# PrototypeVar4_Compactimization.net
KiCad netlist of a schematic drawn in EAGLE
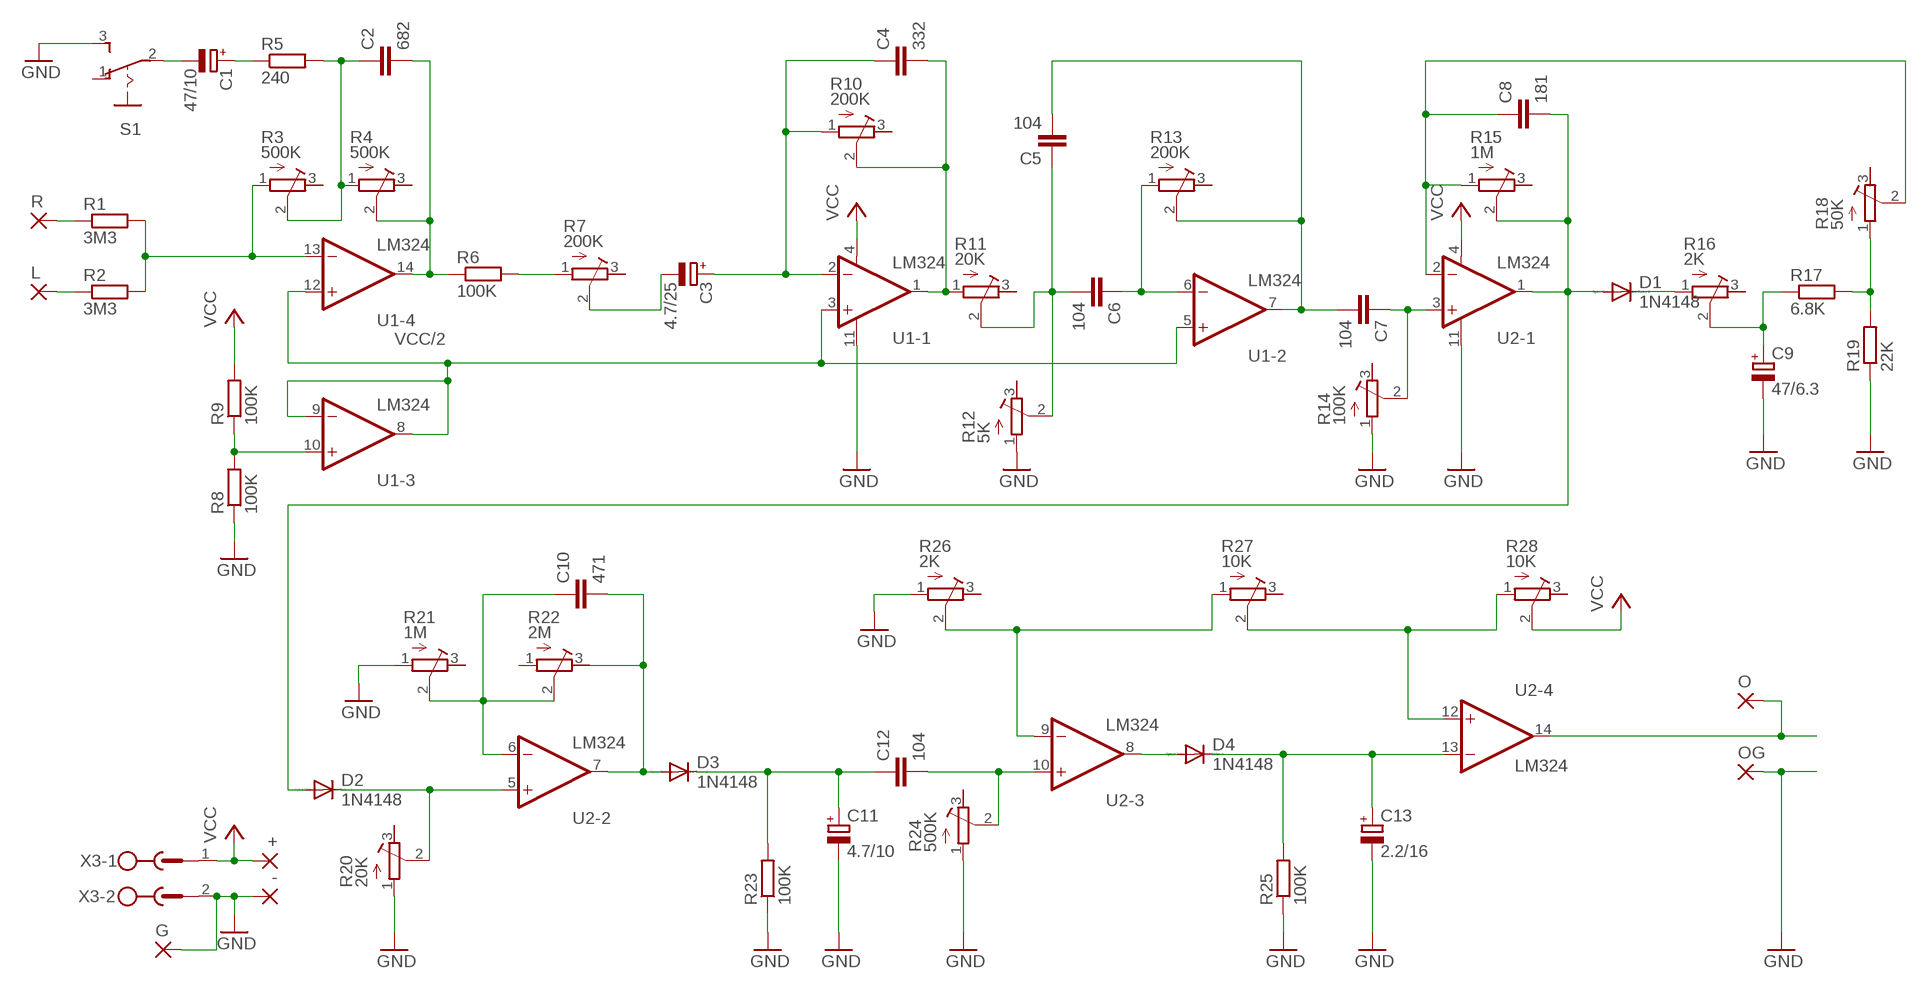
[diagram p0: schematic, sheet 1]

(export (version "E")
  (design (tool "Eeschema 10.0.6"))
  (components
    (comp (ref "+")
      (value "1,6/0,9")
      (footprint "eagle-import:1,6_0,9")
      (libsource (lib "eagle-import") (part "1,6/0,9"))
    )
    (comp (ref "-")
      (value "1,6/0,9")
      (footprint "eagle-import:1,6_0,9")
      (libsource (lib "eagle-import") (part "1,6/0,9"))
    )
    (comp (ref "C1")
      (value "47/10")
      (footprint "eagle-import:E2,5-7")
      (libsource (lib "eagle-import") (part "CPOL-EUE2.5-7"))
    )
    (comp (ref "C2")
      (value "682")
      (footprint "eagle-import:C050-035X075")
      (libsource (lib "eagle-import") (part "C-EU050-035X075"))
    )
    (comp (ref "C3")
      (value "4.7/25")
      (footprint "eagle-import:E2,5-7")
      (libsource (lib "eagle-import") (part "CPOL-EUE2.5-7"))
    )
    (comp (ref "C4")
      (value "332")
      (footprint "eagle-import:C050-035X075")
      (libsource (lib "eagle-import") (part "C-EU050-035X075"))
    )
    (comp (ref "C5")
      (value "104")
      (footprint "eagle-import:C050-035X075")
      (libsource (lib "eagle-import") (part "C-EU050-035X075"))
    )
    (comp (ref "C6")
      (value "104")
      (footprint "eagle-import:C050-035X075")
      (libsource (lib "eagle-import") (part "C-EU050-035X075"))
    )
    (comp (ref "C7")
      (value "104")
      (footprint "eagle-import:C050-035X075")
      (libsource (lib "eagle-import") (part "C-EU050-035X075"))
    )
    (comp (ref "C8")
      (value "181")
      (footprint "eagle-import:C050-035X075")
      (libsource (lib "eagle-import") (part "C-EU050-035X075"))
    )
    (comp (ref "C9")
      (value "47/6.3")
      (footprint "eagle-import:E2,5-7")
      (libsource (lib "eagle-import") (part "CPOL-EUE2.5-7"))
    )
    (comp (ref "C10")
      (value "471")
      (footprint "eagle-import:C050-035X075")
      (libsource (lib "eagle-import") (part "C-EU050-035X075"))
    )
    (comp (ref "C11")
      (value "4.7/10")
      (footprint "eagle-import:E2,5-7")
      (libsource (lib "eagle-import") (part "CPOL-EUE2.5-7"))
    )
    (comp (ref "C12")
      (value "104")
      (footprint "eagle-import:C050-035X075")
      (libsource (lib "eagle-import") (part "C-EU050-035X075"))
    )
    (comp (ref "C13")
      (value "2.2/16")
      (footprint "eagle-import:E2,5-7")
      (libsource (lib "eagle-import") (part "CPOL-EUE2.5-7"))
    )
    (comp (ref "D1")
      (value "1N4148")
      (footprint "eagle-import:DO35-10")
      (libsource (lib "eagle-import") (part "1N4148DO35-10"))
    )
    (comp (ref "D2")
      (value "1N4148")
      (footprint "eagle-import:DO35-10")
      (libsource (lib "eagle-import") (part "1N4148DO35-10"))
    )
    (comp (ref "D3")
      (value "1N4148")
      (footprint "eagle-import:DO35-10")
      (libsource (lib "eagle-import") (part "1N4148DO35-10"))
    )
    (comp (ref "D4")
      (value "1N4148")
      (footprint "eagle-import:DO35-10")
      (libsource (lib "eagle-import") (part "1N4148DO35-10"))
    )
    (comp (ref "G")
      (value "1,6/0,9")
      (footprint "eagle-import:1,6_0,9")
      (libsource (lib "eagle-import") (part "1,6/0,9"))
    )
    (comp (ref "L")
      (value "1,6/0,9")
      (footprint "eagle-import:1,6_0,9")
      (libsource (lib "eagle-import") (part "1,6/0,9"))
    )
    (comp (ref "O")
      (value "1,6/0,9")
      (footprint "eagle-import:1,6_0,9")
      (libsource (lib "eagle-import") (part "1,6/0,9"))
    )
    (comp (ref "OG")
      (value "1,6/0,9")
      (footprint "eagle-import:1,6_0,9")
      (libsource (lib "eagle-import") (part "1,6/0,9"))
    )
    (comp (ref "R")
      (value "1,6/0,8")
      (footprint "eagle-import:1,6_0,8")
      (libsource (lib "eagle-import") (part "1,6/0,8"))
    )
    (comp (ref "R1")
      (value "3M3")
      (footprint "eagle-import:0207_10")
      (libsource (lib "eagle-import") (part "R-EU_0207/10"))
    )
    (comp (ref "R2")
      (value "3M3")
      (footprint "eagle-import:0207_10")
      (libsource (lib "eagle-import") (part "R-EU_0207/10"))
    )
    (comp (ref "R3")
      (value "500K")
      (footprint "eagle-import:RTRIM64W")
      (libsource (lib "eagle-import") (part "R-TRIMM64W"))
    )
    (comp (ref "R4")
      (value "500K")
      (footprint "eagle-import:RTRIM64W")
      (libsource (lib "eagle-import") (part "R-TRIMM64W"))
    )
    (comp (ref "R5")
      (value "240")
      (footprint "eagle-import:0207_10")
      (libsource (lib "eagle-import") (part "R-EU_0207/10"))
    )
    (comp (ref "R6")
      (value "100K")
      (footprint "eagle-import:0207_10")
      (libsource (lib "eagle-import") (part "R-EU_0207/10"))
    )
    (comp (ref "R7")
      (value "200K")
      (footprint "eagle-import:RTRIM64W")
      (libsource (lib "eagle-import") (part "R-TRIMM64W"))
    )
    (comp (ref "R8")
      (value "100K")
      (footprint "eagle-import:0207_10")
      (libsource (lib "eagle-import") (part "R-EU_0207/10"))
    )
    (comp (ref "R9")
      (value "100K")
      (footprint "eagle-import:0207_10")
      (libsource (lib "eagle-import") (part "R-EU_0207/10"))
    )
    (comp (ref "R10")
      (value "200K")
      (footprint "eagle-import:RTRIM64W")
      (libsource (lib "eagle-import") (part "R-TRIMM64W"))
    )
    (comp (ref "R11")
      (value "20K")
      (footprint "eagle-import:RTRIM64W")
      (libsource (lib "eagle-import") (part "R-TRIMM64W"))
    )
    (comp (ref "R12")
      (value "5K")
      (footprint "eagle-import:RTRIM64W")
      (libsource (lib "eagle-import") (part "R-TRIMM64W"))
    )
    (comp (ref "R13")
      (value "200K")
      (footprint "eagle-import:RTRIM64W")
      (libsource (lib "eagle-import") (part "R-TRIMM64W"))
    )
    (comp (ref "R14")
      (value "100K")
      (footprint "eagle-import:RTRIM64W")
      (libsource (lib "eagle-import") (part "R-TRIMM64W"))
    )
    (comp (ref "R15")
      (value "1M")
      (footprint "eagle-import:RTRIM64W")
      (libsource (lib "eagle-import") (part "R-TRIMM64W"))
    )
    (comp (ref "R16")
      (value "2K")
      (footprint "eagle-import:RTRIM64W")
      (libsource (lib "eagle-import") (part "R-TRIMM64W"))
    )
    (comp (ref "R17")
      (value "6.8K")
      (footprint "eagle-import:0207_10")
      (libsource (lib "eagle-import") (part "R-EU_0207/10"))
    )
    (comp (ref "R18")
      (value "50K")
      (footprint "eagle-import:RTRIM64W")
      (libsource (lib "eagle-import") (part "R-TRIMM64W"))
    )
    (comp (ref "R19")
      (value "22K")
      (footprint "eagle-import:0207_10")
      (libsource (lib "eagle-import") (part "R-EU_0207/10"))
    )
    (comp (ref "R20")
      (value "20K")
      (footprint "eagle-import:RTRIM64W")
      (libsource (lib "eagle-import") (part "R-TRIMM64W"))
    )
    (comp (ref "R21")
      (value "1M")
      (footprint "eagle-import:RTRIM64W")
      (libsource (lib "eagle-import") (part "R-TRIMM64W"))
    )
    (comp (ref "R22")
      (value "2M")
      (footprint "eagle-import:RTRIM64W")
      (libsource (lib "eagle-import") (part "R-TRIMM64W"))
    )
    (comp (ref "R23")
      (value "100K")
      (footprint "eagle-import:0207_10")
      (libsource (lib "eagle-import") (part "R-EU_0207/10"))
    )
    (comp (ref "R24")
      (value "500K")
      (footprint "eagle-import:RTRIM64W")
      (libsource (lib "eagle-import") (part "R-TRIMM64W"))
    )
    (comp (ref "R25")
      (value "100K")
      (footprint "eagle-import:0207_10")
      (libsource (lib "eagle-import") (part "R-EU_0207/10"))
    )
    (comp (ref "R26")
      (value "2K")
      (footprint "eagle-import:RTRIM64W")
      (libsource (lib "eagle-import") (part "R-TRIMM64W"))
    )
    (comp (ref "R27")
      (value "10K")
      (footprint "eagle-import:RTRIM64W")
      (libsource (lib "eagle-import") (part "R-TRIMM64W"))
    )
    (comp (ref "R28")
      (value "10K")
      (footprint "eagle-import:RTRIM64W")
      (libsource (lib "eagle-import") (part "R-TRIMM64W"))
    )
    (comp (ref "S1")
      (value "255SB")
      (footprint "eagle-import:255SB")
      (libsource (lib "eagle-import") (part "255SB"))
    )
    (comp (ref "U1-")
      (value "LM324")
      (footprint "eagle-import:SOIC-14")
      (libsource (lib "eagle-import") (part "LM324"))
    )
    (comp (ref "U2-")
      (value "LM324")
      (footprint "eagle-import:SOIC-14")
      (libsource (lib "eagle-import") (part "LM324"))
    )
    (comp (ref "X3")
      (value "MSTBV2")
      (footprint "eagle-import:MSTBV2")
      (libsource (lib "eagle-import") (part "MSTBV2"))
    )
  )
  (nets
    (net (code "1") (name "/VCC{slash}2") (class "Default")
      (node (ref "U1-") (pin "12") (pinfunction "+IN_12") (pintype "input"))
      (node (ref "U1-") (pin "3") (pinfunction "+IN_3") (pintype "input"))
      (node (ref "U1-") (pin "5") (pinfunction "+IN_5") (pintype "input"))
      (node (ref "U1-") (pin "8") (pinfunction "OUT_8") (pintype "output"))
      (node (ref "U1-") (pin "9") (pinfunction "-IN_9") (pintype "input"))
    )
    (net (code "2") (name "GND") (class "Default")
      (node (ref "-") (pin "1") (pinfunction "P_1") (pintype "passive"))
      (node (ref "C11") (pin "-") (pinfunction "-_-") (pintype "passive"))
      (node (ref "C13") (pin "-") (pinfunction "-_-") (pintype "passive"))
      (node (ref "C9") (pin "-") (pinfunction "-_-") (pintype "passive"))
      (node (ref "G") (pin "1") (pinfunction "P_1") (pintype "passive"))
      (node (ref "OG") (pin "1") (pinfunction "P_1") (pintype "passive"))
      (node (ref "R12") (pin "1") (pinfunction "A_1") (pintype "passive"))
      (node (ref "R14") (pin "1") (pinfunction "A_1") (pintype "passive"))
      (node (ref "R19") (pin "1") (pinfunction "1_1") (pintype "passive"))
      (node (ref "R20") (pin "1") (pinfunction "A_1") (pintype "passive"))
      (node (ref "R21") (pin "1") (pinfunction "A_1") (pintype "passive"))
      (node (ref "R23") (pin "1") (pinfunction "1_1") (pintype "passive"))
      (node (ref "R24") (pin "1") (pinfunction "A_1") (pintype "passive"))
      (node (ref "R25") (pin "1") (pinfunction "1_1") (pintype "passive"))
      (node (ref "R26") (pin "1") (pinfunction "A_1") (pintype "passive"))
      (node (ref "R8") (pin "1") (pinfunction "1_1") (pintype "passive"))
      (node (ref "S1") (pin "3") (pinfunction "S_3") (pintype "passive"))
      (node (ref "U1-") (pin "11") (pinfunction "V-_11") (pintype "power_in"))
      (node (ref "U2-") (pin "11") (pinfunction "V-_11") (pintype "power_in"))
      (node (ref "X3") (pin "2") (pinfunction "SK_2") (pintype "passive"))
    )
    (net (code "3") (name "Net-(C1-Pad+)") (class "Default")
      (node (ref "C1") (pin "+") (pinfunction "+_+") (pintype "passive"))
      (node (ref "R5") (pin "1") (pinfunction "1_1") (pintype "passive"))
    )
    (net (code "4") (name "Net-(C11-Pad+)") (class "Default")
      (node (ref "C11") (pin "+") (pinfunction "+_+") (pintype "passive"))
      (node (ref "C12") (pin "1") (pinfunction "1_1") (pintype "passive"))
      (node (ref "D3") (pin "C") (pinfunction "C_C") (pintype "passive"))
      (node (ref "R23") (pin "2") (pinfunction "2_2") (pintype "passive"))
    )
    (net (code "5") (name "Net-(L-P)") (class "Default")
      (node (ref "L") (pin "1") (pinfunction "P_1") (pintype "passive"))
      (node (ref "R2") (pin "1") (pinfunction "1_1") (pintype "passive"))
    )
    (net (code "6") (name "Net-(O-P)") (class "Default")
      (node (ref "O") (pin "1") (pinfunction "P_1") (pintype "passive"))
      (node (ref "U2-") (pin "14") (pinfunction "OUT_14") (pintype "output"))
    )
    (net (code "7") (name "Net-(R-P)") (class "Default")
      (node (ref "R") (pin "1") (pinfunction "P_1") (pintype "passive"))
      (node (ref "R1") (pin "1") (pinfunction "1_1") (pintype "passive"))
    )
    (net (code "8") (name "Net-(R3-A)") (class "Default")
      (node (ref "R1") (pin "2") (pinfunction "2_2") (pintype "passive"))
      (node (ref "R2") (pin "2") (pinfunction "2_2") (pintype "passive"))
      (node (ref "R3") (pin "1") (pinfunction "A_1") (pintype "passive"))
      (node (ref "U1-") (pin "13") (pinfunction "-IN_13") (pintype "input"))
    )
    (net (code "9") (name "Net-(R3-S)") (class "Default")
      (node (ref "C2") (pin "1") (pinfunction "1_1") (pintype "passive"))
      (node (ref "R3") (pin "2") (pinfunction "S_2") (pintype "passive"))
      (node (ref "R4") (pin "1") (pinfunction "A_1") (pintype "passive"))
      (node (ref "R5") (pin "2") (pinfunction "2_2") (pintype "passive"))
    )
    (net (code "10") (name "Net-(R4-S)") (class "Default")
      (node (ref "C2") (pin "2") (pinfunction "2_2") (pintype "passive"))
      (node (ref "R4") (pin "2") (pinfunction "S_2") (pintype "passive"))
      (node (ref "R6") (pin "1") (pinfunction "1_1") (pintype "passive"))
      (node (ref "U1-") (pin "14") (pinfunction "OUT_14") (pintype "output"))
    )
    (net (code "11") (name "Net-(R7-A)") (class "Default")
      (node (ref "R6") (pin "2") (pinfunction "2_2") (pintype "passive"))
      (node (ref "R7") (pin "1") (pinfunction "A_1") (pintype "passive"))
    )
    (net (code "12") (name "Net-(R7-S)") (class "Default")
      (node (ref "C3") (pin "-") (pinfunction "-_-") (pintype "passive"))
      (node (ref "R7") (pin "2") (pinfunction "S_2") (pintype "passive"))
    )
    (net (code "13") (name "Net-(R10-A)") (class "Default")
      (node (ref "C3") (pin "+") (pinfunction "+_+") (pintype "passive"))
      (node (ref "C4") (pin "1") (pinfunction "1_1") (pintype "passive"))
      (node (ref "R10") (pin "1") (pinfunction "A_1") (pintype "passive"))
      (node (ref "U1-") (pin "2") (pinfunction "-IN_2") (pintype "input"))
    )
    (net (code "14") (name "Net-(R10-S)") (class "Default")
      (node (ref "C4") (pin "2") (pinfunction "2_2") (pintype "passive"))
      (node (ref "R10") (pin "2") (pinfunction "S_2") (pintype "passive"))
      (node (ref "R11") (pin "1") (pinfunction "A_1") (pintype "passive"))
      (node (ref "U1-") (pin "1") (pinfunction "OUT_1") (pintype "output"))
    )
    (net (code "15") (name "Net-(R11-S)") (class "Default")
      (node (ref "C5") (pin "1") (pinfunction "1_1") (pintype "passive"))
      (node (ref "C6") (pin "2") (pinfunction "2_2") (pintype "passive"))
      (node (ref "R11") (pin "2") (pinfunction "S_2") (pintype "passive"))
      (node (ref "R12") (pin "2") (pinfunction "S_2") (pintype "passive"))
    )
    (net (code "16") (name "Net-(R13-A)") (class "Default")
      (node (ref "C6") (pin "1") (pinfunction "1_1") (pintype "passive"))
      (node (ref "R13") (pin "1") (pinfunction "A_1") (pintype "passive"))
      (node (ref "U1-") (pin "6") (pinfunction "-IN_6") (pintype "input"))
    )
    (net (code "17") (name "Net-(R13-S)") (class "Default")
      (node (ref "C5") (pin "2") (pinfunction "2_2") (pintype "passive"))
      (node (ref "C7") (pin "2") (pinfunction "2_2") (pintype "passive"))
      (node (ref "R13") (pin "2") (pinfunction "S_2") (pintype "passive"))
      (node (ref "U1-") (pin "7") (pinfunction "OUT_7") (pintype "output"))
    )
    (net (code "18") (name "Net-(R14-S)") (class "Default")
      (node (ref "C7") (pin "1") (pinfunction "1_1") (pintype "passive"))
      (node (ref "R14") (pin "2") (pinfunction "S_2") (pintype "passive"))
      (node (ref "U2-") (pin "3") (pinfunction "+IN_3") (pintype "input"))
    )
    (net (code "19") (name "Net-(R15-A)") (class "Default")
      (node (ref "C8") (pin "1") (pinfunction "1_1") (pintype "passive"))
      (node (ref "R15") (pin "1") (pinfunction "A_1") (pintype "passive"))
      (node (ref "R18") (pin "2") (pinfunction "S_2") (pintype "passive"))
      (node (ref "U2-") (pin "2") (pinfunction "-IN_2") (pintype "input"))
    )
    (net (code "20") (name "Net-(R15-S)") (class "Default")
      (node (ref "C8") (pin "2") (pinfunction "2_2") (pintype "passive"))
      (node (ref "D1") (pin "A") (pinfunction "A_A") (pintype "passive"))
      (node (ref "D2") (pin "A") (pinfunction "A_A") (pintype "passive"))
      (node (ref "R15") (pin "2") (pinfunction "S_2") (pintype "passive"))
      (node (ref "U2-") (pin "1") (pinfunction "OUT_1") (pintype "output"))
    )
    (net (code "21") (name "Net-(R16-A)") (class "Default")
      (node (ref "D1") (pin "C") (pinfunction "C_C") (pintype "passive"))
      (node (ref "R16") (pin "1") (pinfunction "A_1") (pintype "passive"))
    )
    (net (code "22") (name "Net-(R16-S)") (class "Default")
      (node (ref "C9") (pin "+") (pinfunction "+_+") (pintype "passive"))
      (node (ref "R16") (pin "2") (pinfunction "S_2") (pintype "passive"))
      (node (ref "R17") (pin "1") (pinfunction "1_1") (pintype "passive"))
    )
    (net (code "23") (name "Net-(R18-A)") (class "Default")
      (node (ref "R17") (pin "2") (pinfunction "2_2") (pintype "passive"))
      (node (ref "R18") (pin "1") (pinfunction "A_1") (pintype "passive"))
      (node (ref "R19") (pin "2") (pinfunction "2_2") (pintype "passive"))
    )
    (net (code "24") (name "Net-(R20-S)") (class "Default")
      (node (ref "D2") (pin "C") (pinfunction "C_C") (pintype "passive"))
      (node (ref "R20") (pin "2") (pinfunction "S_2") (pintype "passive"))
      (node (ref "U2-") (pin "5") (pinfunction "+IN_5") (pintype "input"))
    )
    (net (code "25") (name "Net-(R21-S)") (class "Default")
      (node (ref "C10") (pin "1") (pinfunction "1_1") (pintype "passive"))
      (node (ref "R21") (pin "2") (pinfunction "S_2") (pintype "passive"))
      (node (ref "R22") (pin "2") (pinfunction "S_2") (pintype "passive"))
      (node (ref "U2-") (pin "6") (pinfunction "-IN_6") (pintype "input"))
    )
    (net (code "26") (name "Net-(R22-E)") (class "Default")
      (node (ref "C10") (pin "2") (pinfunction "2_2") (pintype "passive"))
      (node (ref "D3") (pin "A") (pinfunction "A_A") (pintype "passive"))
      (node (ref "R22") (pin "3") (pinfunction "E_3") (pintype "passive"))
      (node (ref "U2-") (pin "7") (pinfunction "OUT_7") (pintype "output"))
    )
    (net (code "27") (name "Net-(R24-S)") (class "Default")
      (node (ref "C12") (pin "2") (pinfunction "2_2") (pintype "passive"))
      (node (ref "R24") (pin "2") (pinfunction "S_2") (pintype "passive"))
      (node (ref "U2-") (pin "10") (pinfunction "+IN_10") (pintype "input"))
    )
    (net (code "28") (name "Net-(R26-S)") (class "Default")
      (node (ref "R26") (pin "2") (pinfunction "S_2") (pintype "passive"))
      (node (ref "R27") (pin "1") (pinfunction "A_1") (pintype "passive"))
      (node (ref "U2-") (pin "9") (pinfunction "-IN_9") (pintype "input"))
    )
    (net (code "29") (name "Net-(R27-S)") (class "Default")
      (node (ref "R27") (pin "2") (pinfunction "S_2") (pintype "passive"))
      (node (ref "R28") (pin "1") (pinfunction "A_1") (pintype "passive"))
      (node (ref "U2-") (pin "12") (pinfunction "+IN_12") (pintype "input"))
    )
    (net (code "30") (name "Net-(S1-P)") (class "Default")
      (node (ref "C1") (pin "-") (pinfunction "-_-") (pintype "passive"))
      (node (ref "S1") (pin "2") (pinfunction "P_2") (pintype "passive"))
    )
    (net (code "31") (name "Net-(U1-C-+IN)") (class "Default")
      (node (ref "R8") (pin "2") (pinfunction "2_2") (pintype "passive"))
      (node (ref "R9") (pin "1") (pinfunction "1_1") (pintype "passive"))
      (node (ref "U1-") (pin "10") (pinfunction "+IN_10") (pintype "input"))
    )
    (net (code "32") (name "Net-(U2-C-OUT)") (class "Default")
      (node (ref "D4") (pin "A") (pinfunction "A_A") (pintype "passive"))
      (node (ref "U2-") (pin "8") (pinfunction "OUT_8") (pintype "output"))
    )
    (net (code "33") (name "Net-(U2-D--IN)") (class "Default")
      (node (ref "C13") (pin "+") (pinfunction "+_+") (pintype "passive"))
      (node (ref "D4") (pin "C") (pinfunction "C_C") (pintype "passive"))
      (node (ref "R25") (pin "2") (pinfunction "2_2") (pintype "passive"))
      (node (ref "U2-") (pin "13") (pinfunction "-IN_13") (pintype "input"))
    )
    (net (code "34") (name "VCC") (class "Default")
      (node (ref "+") (pin "1") (pinfunction "P_1") (pintype "passive"))
      (node (ref "R28") (pin "2") (pinfunction "S_2") (pintype "passive"))
      (node (ref "R9") (pin "2") (pinfunction "2_2") (pintype "passive"))
      (node (ref "U1-") (pin "4") (pinfunction "V+_4") (pintype "power_in"))
      (node (ref "U2-") (pin "4") (pinfunction "V+_4") (pintype "power_in"))
      (node (ref "X3") (pin "1") (pinfunction "SK_1") (pintype "passive"))
    )
    (net (code "35") (name "unconnected-(R3-E-Pad3)") (class "Default")
      (node (ref "R3") (pin "3") (pinfunction "E_3") (pintype "passive"))
    )
    (net (code "36") (name "unconnected-(R4-E-Pad3)") (class "Default")
      (node (ref "R4") (pin "3") (pinfunction "E_3") (pintype "passive"))
    )
    (net (code "37") (name "unconnected-(R7-E-Pad3)") (class "Default")
      (node (ref "R7") (pin "3") (pinfunction "E_3") (pintype "passive"))
    )
    (net (code "38") (name "unconnected-(R10-E-Pad3)") (class "Default")
      (node (ref "R10") (pin "3") (pinfunction "E_3") (pintype "passive"))
    )
    (net (code "39") (name "unconnected-(R11-E-Pad3)") (class "Default")
      (node (ref "R11") (pin "3") (pinfunction "E_3") (pintype "passive"))
    )
    (net (code "40") (name "unconnected-(R12-E-Pad3)") (class "Default")
      (node (ref "R12") (pin "3") (pinfunction "E_3") (pintype "passive"))
    )
    (net (code "41") (name "unconnected-(R13-E-Pad3)") (class "Default")
      (node (ref "R13") (pin "3") (pinfunction "E_3") (pintype "passive"))
    )
    (net (code "42") (name "unconnected-(R14-E-Pad3)") (class "Default")
      (node (ref "R14") (pin "3") (pinfunction "E_3") (pintype "passive"))
    )
    (net (code "43") (name "unconnected-(R15-E-Pad3)") (class "Default")
      (node (ref "R15") (pin "3") (pinfunction "E_3") (pintype "passive"))
    )
    (net (code "44") (name "unconnected-(R16-E-Pad3)") (class "Default")
      (node (ref "R16") (pin "3") (pinfunction "E_3") (pintype "passive"))
    )
    (net (code "45") (name "unconnected-(R18-E-Pad3)") (class "Default")
      (node (ref "R18") (pin "3") (pinfunction "E_3") (pintype "passive"))
    )
    (net (code "46") (name "unconnected-(R20-E-Pad3)") (class "Default")
      (node (ref "R20") (pin "3") (pinfunction "E_3") (pintype "passive"))
    )
    (net (code "47") (name "unconnected-(R21-E-Pad3)") (class "Default")
      (node (ref "R21") (pin "3") (pinfunction "E_3") (pintype "passive"))
    )
    (net (code "48") (name "unconnected-(R22-A-Pad1)") (class "Default")
      (node (ref "R22") (pin "1") (pinfunction "A_1") (pintype "passive"))
    )
    (net (code "49") (name "unconnected-(R24-E-Pad3)") (class "Default")
      (node (ref "R24") (pin "3") (pinfunction "E_3") (pintype "passive"))
    )
    (net (code "50") (name "unconnected-(R26-E-Pad3)") (class "Default")
      (node (ref "R26") (pin "3") (pinfunction "E_3") (pintype "passive"))
    )
    (net (code "51") (name "unconnected-(R27-E-Pad3)") (class "Default")
      (node (ref "R27") (pin "3") (pinfunction "E_3") (pintype "passive"))
    )
    (net (code "52") (name "unconnected-(R28-E-Pad3)") (class "Default")
      (node (ref "R28") (pin "3") (pinfunction "E_3") (pintype "passive"))
    )
    (net (code "53") (name "unconnected-(S1-O-Pad1)") (class "Default")
      (node (ref "S1") (pin "1") (pinfunction "O_1") (pintype "passive"))
    )
  )
)
